# HSIO.net
KiCad netlist of a schematic drawn in EAGLE
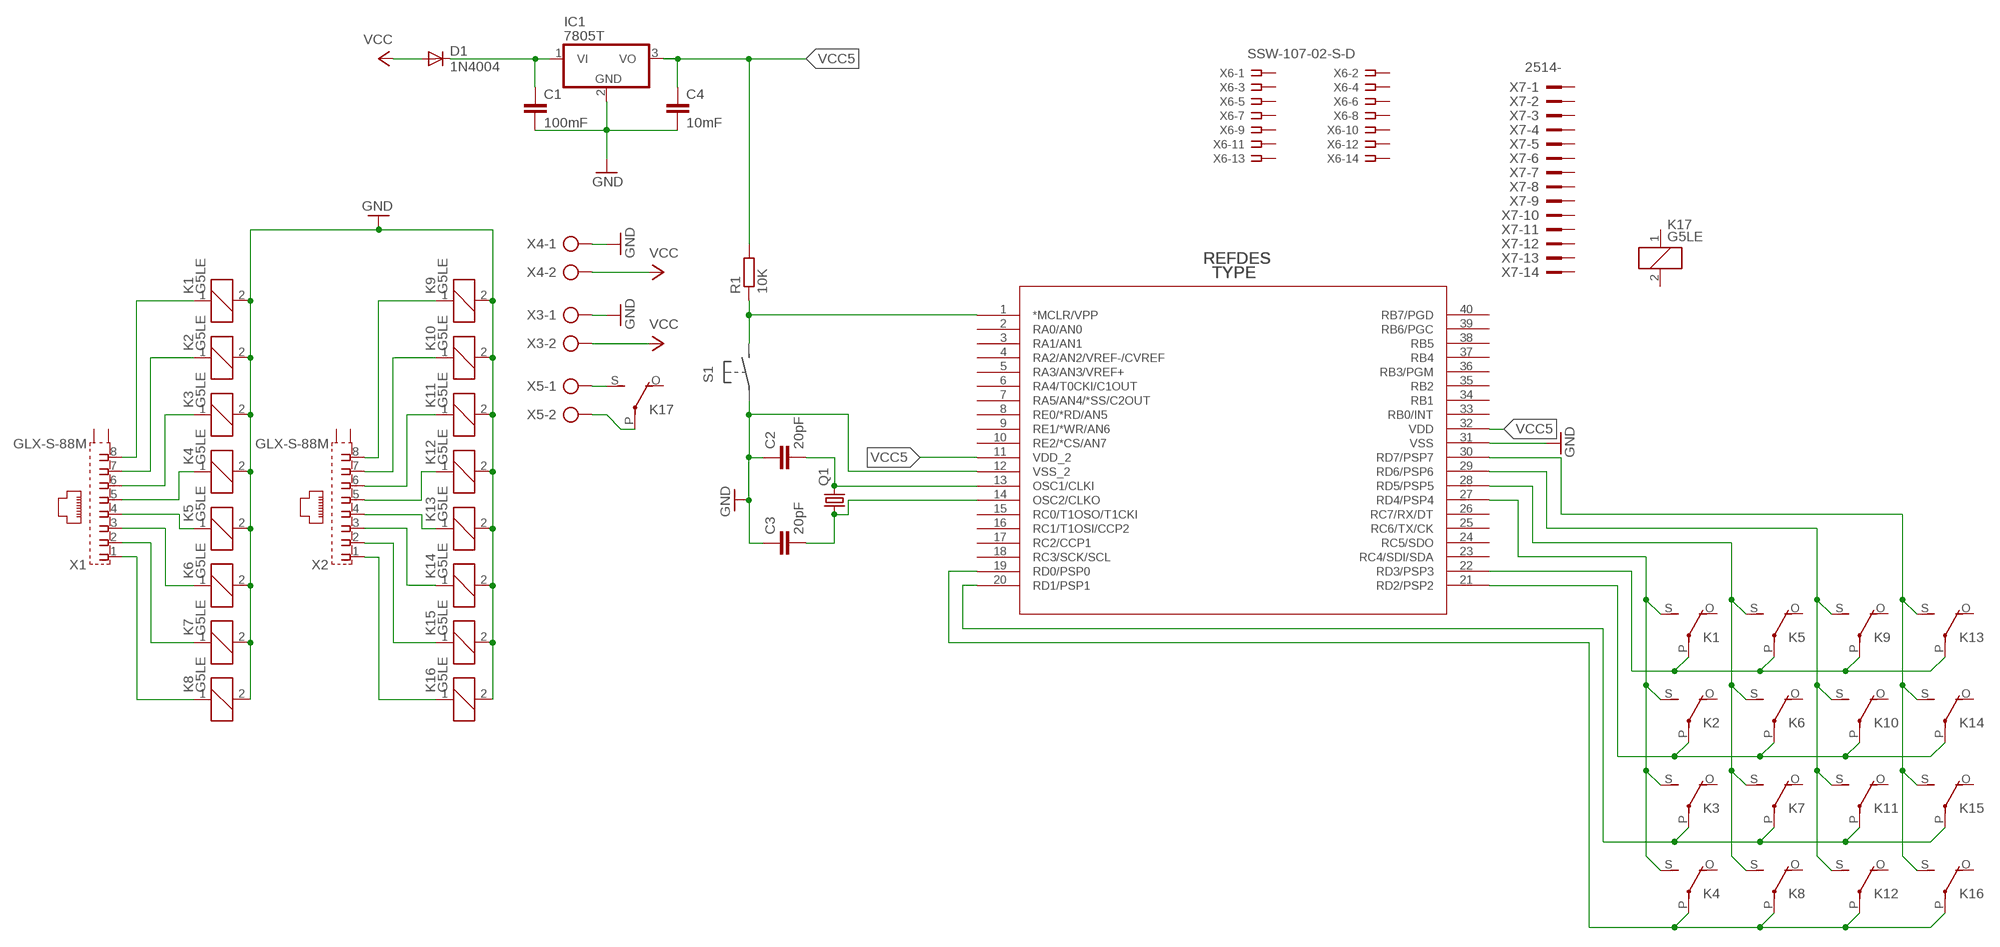
[diagram p0: schematic, sheet 1]

(export (version "E")
  (design (tool "Eeschema 10.0.6"))
  (components
    (comp (ref "C1")
      (value "100mF")
      (footprint "eagle-import:C10B4")
      (libsource (lib "eagle-import") (part "C10/4"))
    )
    (comp (ref "C2")
      (value "20pF")
      (footprint "eagle-import:C10B4")
      (libsource (lib "eagle-import") (part "C10/4"))
    )
    (comp (ref "C3")
      (value "20pF")
      (footprint "eagle-import:C10B4")
      (libsource (lib "eagle-import") (part "C10/4"))
    )
    (comp (ref "C4")
      (value "10mF")
      (footprint "eagle-import:C10B4")
      (libsource (lib "eagle-import") (part "C10/4"))
    )
    (comp (ref "D1")
      (value "1N4004")
      (footprint "eagle-import:DO41-10")
      (libsource (lib "eagle-import") (part "1N4004"))
    )
    (comp (ref "IC1")
      (value "7805T")
      (footprint "eagle-import:TO220H")
      (libsource (lib "eagle-import") (part "78T05"))
    )
    (comp (ref "K1")
      (value "G5LE")
      (footprint "eagle-import:G5LE")
      (libsource (lib "eagle-import") (part "G5LE"))
    )
    (comp (ref "K2")
      (value "G5LE")
      (footprint "eagle-import:G5LE")
      (libsource (lib "eagle-import") (part "G5LE"))
    )
    (comp (ref "K3")
      (value "G5LE")
      (footprint "eagle-import:G5LE")
      (libsource (lib "eagle-import") (part "G5LE"))
    )
    (comp (ref "K4")
      (value "G5LE")
      (footprint "eagle-import:G5LE")
      (libsource (lib "eagle-import") (part "G5LE"))
    )
    (comp (ref "K5")
      (value "G5LE")
      (footprint "eagle-import:G5LE")
      (libsource (lib "eagle-import") (part "G5LE"))
    )
    (comp (ref "K6")
      (value "G5LE")
      (footprint "eagle-import:G5LE")
      (libsource (lib "eagle-import") (part "G5LE"))
    )
    (comp (ref "K7")
      (value "G5LE")
      (footprint "eagle-import:G5LE")
      (libsource (lib "eagle-import") (part "G5LE"))
    )
    (comp (ref "K8")
      (value "G5LE")
      (footprint "eagle-import:G5LE")
      (libsource (lib "eagle-import") (part "G5LE"))
    )
    (comp (ref "K9")
      (value "G5LE")
      (footprint "eagle-import:G5LE")
      (libsource (lib "eagle-import") (part "G5LE"))
    )
    (comp (ref "K10")
      (value "G5LE")
      (footprint "eagle-import:G5LE")
      (libsource (lib "eagle-import") (part "G5LE"))
    )
    (comp (ref "K11")
      (value "G5LE")
      (footprint "eagle-import:G5LE")
      (libsource (lib "eagle-import") (part "G5LE"))
    )
    (comp (ref "K12")
      (value "G5LE")
      (footprint "eagle-import:G5LE")
      (libsource (lib "eagle-import") (part "G5LE"))
    )
    (comp (ref "K13")
      (value "G5LE")
      (footprint "eagle-import:G5LE")
      (libsource (lib "eagle-import") (part "G5LE"))
    )
    (comp (ref "K14")
      (value "G5LE")
      (footprint "eagle-import:G5LE")
      (libsource (lib "eagle-import") (part "G5LE"))
    )
    (comp (ref "K15")
      (value "G5LE")
      (footprint "eagle-import:G5LE")
      (libsource (lib "eagle-import") (part "G5LE"))
    )
    (comp (ref "K16")
      (value "G5LE")
      (footprint "eagle-import:G5LE")
      (libsource (lib "eagle-import") (part "G5LE"))
    )
    (comp (ref "K17")
      (value "G5LE")
      (footprint "eagle-import:G5LE")
      (libsource (lib "eagle-import") (part "G5LE"))
    )
    (comp (ref "Q1")
      (value "CRYSTALHC49S")
      (footprint "eagle-import:HC49_S")
      (libsource (lib "eagle-import") (part "CRYSTALHC49S"))
    )
    (comp (ref "R1")
      (value "10K")
      (footprint "eagle-import:0207_10")
      (libsource (lib "eagle-import") (part "R-EU_0207/10"))
    )
    (comp (ref "U$1")
      (value "PIC16F877A-X/P")
      (footprint "eagle-import:PDIP40_600MC")
      (libsource (lib "eagle-import") (part "PIC16F877A-X/P"))
    )
    (comp (ref "X1")
      (value "GLX-S-88M")
      (footprint "eagle-import:GLX-S-88M")
      (libsource (lib "eagle-import") (part "GLX-S-88M"))
    )
    (comp (ref "X2")
      (value "GLX-S-88M")
      (footprint "eagle-import:GLX-S-88M")
      (libsource (lib "eagle-import") (part "GLX-S-88M"))
    )
    (comp (ref "X3")
      (value "AK300/2")
      (footprint "eagle-import:AK300_2")
      (libsource (lib "eagle-import") (part "AK300/2"))
    )
    (comp (ref "X4")
      (value "AK300/2")
      (footprint "eagle-import:AK300_2")
      (libsource (lib "eagle-import") (part "AK300/2"))
    )
    (comp (ref "X5")
      (value "AK300/2")
      (footprint "eagle-import:AK300_2")
      (libsource (lib "eagle-import") (part "AK300/2"))
    )
    (comp (ref "X6")
      (value "SSW-107-02-S-D")
      (footprint "eagle-import:SSW-107-02-S-D")
      (libsource (lib "eagle-import") (part "SSW-107-02-S-D"))
    )
    (comp (ref "X7")
      (value "2514-")
      (footprint "eagle-import:PAK100_2500-14")
      (libsource (lib "eagle-import") (part "2514-"))
    )
  )
  (nets
    (net (code "1") (name "GND") (class "Default")
      (node (ref "C1") (pin "2") (pinfunction "2_2") (pintype "passive"))
      (node (ref "C2") (pin "1") (pinfunction "1_1") (pintype "passive"))
      (node (ref "C3") (pin "1") (pinfunction "1_1") (pintype "passive"))
      (node (ref "C4") (pin "2") (pinfunction "2_2") (pintype "passive"))
      (node (ref "IC1") (pin "2") (pinfunction "GND_2") (pintype "passive"))
      (node (ref "K1") (pin "2") (pinfunction "2_2") (pintype "passive"))
      (node (ref "K10") (pin "2") (pinfunction "2_2") (pintype "passive"))
      (node (ref "K11") (pin "2") (pinfunction "2_2") (pintype "passive"))
      (node (ref "K12") (pin "2") (pinfunction "2_2") (pintype "passive"))
      (node (ref "K13") (pin "2") (pinfunction "2_2") (pintype "passive"))
      (node (ref "K14") (pin "2") (pinfunction "2_2") (pintype "passive"))
      (node (ref "K15") (pin "2") (pinfunction "2_2") (pintype "passive"))
      (node (ref "K16") (pin "2") (pinfunction "2_2") (pintype "passive"))
      (node (ref "K2") (pin "2") (pinfunction "2_2") (pintype "passive"))
      (node (ref "K3") (pin "2") (pinfunction "2_2") (pintype "passive"))
      (node (ref "K4") (pin "2") (pinfunction "2_2") (pintype "passive"))
      (node (ref "K5") (pin "2") (pinfunction "2_2") (pintype "passive"))
      (node (ref "K6") (pin "2") (pinfunction "2_2") (pintype "passive"))
      (node (ref "K7") (pin "2") (pinfunction "2_2") (pintype "passive"))
      (node (ref "K8") (pin "2") (pinfunction "2_2") (pintype "passive"))
      (node (ref "K9") (pin "2") (pinfunction "2_2") (pintype "passive"))
      (node (ref "U$1") (pin "12") (pinfunction "VSS_2_12") (pintype "passive"))
      (node (ref "U$1") (pin "31") (pinfunction "VSS_31") (pintype "passive"))
      (node (ref "X3") (pin "1") (pinfunction "KL_1") (pintype "passive"))
      (node (ref "X4") (pin "1") (pinfunction "KL_1") (pintype "passive"))
    )
    (net (code "2") (name "Net-(IC1-VI)") (class "Default")
      (node (ref "C1") (pin "1") (pinfunction "1_1") (pintype "passive"))
      (node (ref "D1") (pin "C") (pinfunction "C_C") (pintype "passive"))
      (node (ref "IC1") (pin "1") (pinfunction "VI_1") (pintype "input"))
    )
    (net (code "3") (name "Net-(K1-Pad1)") (class "Default")
      (node (ref "K1") (pin "1") (pinfunction "1_1") (pintype "passive"))
      (node (ref "X1") (pin "8") (pinfunction "8_8") (pintype "passive"))
    )
    (net (code "4") (name "Net-(K2-Pad1)") (class "Default")
      (node (ref "K2") (pin "1") (pinfunction "1_1") (pintype "passive"))
      (node (ref "X1") (pin "7") (pinfunction "7_7") (pintype "passive"))
    )
    (net (code "5") (name "Net-(K3-Pad1)") (class "Default")
      (node (ref "K3") (pin "1") (pinfunction "1_1") (pintype "passive"))
      (node (ref "X1") (pin "6") (pinfunction "6_6") (pintype "passive"))
    )
    (net (code "6") (name "Net-(K4-Pad1)") (class "Default")
      (node (ref "K4") (pin "1") (pinfunction "1_1") (pintype "passive"))
      (node (ref "X1") (pin "5") (pinfunction "5_5") (pintype "passive"))
    )
    (net (code "7") (name "Net-(K5-Pad1)") (class "Default")
      (node (ref "K5") (pin "1") (pinfunction "1_1") (pintype "passive"))
      (node (ref "X1") (pin "4") (pinfunction "4_4") (pintype "passive"))
    )
    (net (code "8") (name "Net-(K6-Pad1)") (class "Default")
      (node (ref "K6") (pin "1") (pinfunction "1_1") (pintype "passive"))
      (node (ref "X1") (pin "3") (pinfunction "3_3") (pintype "passive"))
    )
    (net (code "9") (name "Net-(K7-Pad1)") (class "Default")
      (node (ref "K7") (pin "1") (pinfunction "1_1") (pintype "passive"))
      (node (ref "X1") (pin "2") (pinfunction "2_2") (pintype "passive"))
    )
    (net (code "10") (name "Net-(K8-Pad1)") (class "Default")
      (node (ref "K8") (pin "1") (pinfunction "1_1") (pintype "passive"))
      (node (ref "X1") (pin "1") (pinfunction "1_1") (pintype "passive"))
    )
    (net (code "11") (name "Net-(K9-Pad1)") (class "Default")
      (node (ref "K9") (pin "1") (pinfunction "1_1") (pintype "passive"))
      (node (ref "X2") (pin "8") (pinfunction "8_8") (pintype "passive"))
    )
    (net (code "12") (name "Net-(K10-Pad1)") (class "Default")
      (node (ref "K10") (pin "1") (pinfunction "1_1") (pintype "passive"))
      (node (ref "X2") (pin "7") (pinfunction "7_7") (pintype "passive"))
    )
    (net (code "13") (name "Net-(K11-Pad1)") (class "Default")
      (node (ref "K11") (pin "1") (pinfunction "1_1") (pintype "passive"))
      (node (ref "X2") (pin "6") (pinfunction "6_6") (pintype "passive"))
    )
    (net (code "14") (name "Net-(K12-Pad1)") (class "Default")
      (node (ref "K12") (pin "1") (pinfunction "1_1") (pintype "passive"))
      (node (ref "X2") (pin "5") (pinfunction "5_5") (pintype "passive"))
    )
    (net (code "15") (name "Net-(K13-Pad1)") (class "Default")
      (node (ref "K13") (pin "1") (pinfunction "1_1") (pintype "passive"))
      (node (ref "X2") (pin "4") (pinfunction "4_4") (pintype "passive"))
    )
    (net (code "16") (name "Net-(K14-Pad1)") (class "Default")
      (node (ref "K14") (pin "1") (pinfunction "1_1") (pintype "passive"))
      (node (ref "X2") (pin "3") (pinfunction "3_3") (pintype "passive"))
    )
    (net (code "17") (name "Net-(K15-Pad1)") (class "Default")
      (node (ref "K15") (pin "1") (pinfunction "1_1") (pintype "passive"))
      (node (ref "X2") (pin "2") (pinfunction "2_2") (pintype "passive"))
    )
    (net (code "18") (name "Net-(K16-Pad1)") (class "Default")
      (node (ref "K16") (pin "1") (pinfunction "1_1") (pintype "passive"))
      (node (ref "X2") (pin "1") (pinfunction "1_1") (pintype "passive"))
    )
    (net (code "19") (name "Net-(U$1-*MCLR{slash}VPP)") (class "Default")
      (node (ref "R1") (pin "1") (pinfunction "1_1") (pintype "passive"))
      (node (ref "U$1") (pin "1") (pinfunction "*MCLR/VPP_1") (pintype "passive"))
    )
    (net (code "20") (name "Net-(U$1-OSC1{slash}CLKI)") (class "Default")
      (node (ref "C2") (pin "2") (pinfunction "2_2") (pintype "passive"))
      (node (ref "Q1") (pin "2") (pinfunction "2_2") (pintype "passive"))
      (node (ref "U$1") (pin "13") (pinfunction "OSC1/CLKI_13") (pintype "passive"))
    )
    (net (code "21") (name "Net-(U$1-OSC2{slash}CLKO)") (class "Default")
      (node (ref "C3") (pin "2") (pinfunction "2_2") (pintype "passive"))
      (node (ref "Q1") (pin "1") (pinfunction "1_1") (pintype "passive"))
      (node (ref "U$1") (pin "14") (pinfunction "OSC2/CLKO_14") (pintype "passive"))
    )
    (net (code "22") (name "Net-(U$1-RD0{slash}PSP0)") (class "Default")
      (node (ref "K12") (pin "P") (pinfunction "P_P") (pintype "passive"))
      (node (ref "K16") (pin "P") (pinfunction "P_P") (pintype "passive"))
      (node (ref "K4") (pin "P") (pinfunction "P_P") (pintype "passive"))
      (node (ref "K8") (pin "P") (pinfunction "P_P") (pintype "passive"))
      (node (ref "U$1") (pin "19") (pinfunction "RD0/PSP0_19") (pintype "passive"))
    )
    (net (code "23") (name "Net-(U$1-RD1{slash}PSP1)") (class "Default")
      (node (ref "K11") (pin "P") (pinfunction "P_P") (pintype "passive"))
      (node (ref "K15") (pin "P") (pinfunction "P_P") (pintype "passive"))
      (node (ref "K3") (pin "P") (pinfunction "P_P") (pintype "passive"))
      (node (ref "K7") (pin "P") (pinfunction "P_P") (pintype "passive"))
      (node (ref "U$1") (pin "20") (pinfunction "RD1/PSP1_20") (pintype "passive"))
    )
    (net (code "24") (name "Net-(U$1-RD2{slash}PSP2)") (class "Default")
      (node (ref "K10") (pin "P") (pinfunction "P_P") (pintype "passive"))
      (node (ref "K14") (pin "P") (pinfunction "P_P") (pintype "passive"))
      (node (ref "K2") (pin "P") (pinfunction "P_P") (pintype "passive"))
      (node (ref "K6") (pin "P") (pinfunction "P_P") (pintype "passive"))
      (node (ref "U$1") (pin "21") (pinfunction "RD2/PSP2_21") (pintype "passive"))
    )
    (net (code "25") (name "Net-(U$1-RD3{slash}PSP3)") (class "Default")
      (node (ref "K1") (pin "P") (pinfunction "P_P") (pintype "passive"))
      (node (ref "K13") (pin "P") (pinfunction "P_P") (pintype "passive"))
      (node (ref "K5") (pin "P") (pinfunction "P_P") (pintype "passive"))
      (node (ref "K9") (pin "P") (pinfunction "P_P") (pintype "passive"))
      (node (ref "U$1") (pin "22") (pinfunction "RD3/PSP3_22") (pintype "passive"))
    )
    (net (code "26") (name "Net-(U$1-RD4{slash}PSP4)") (class "Default")
      (node (ref "K1") (pin "S") (pinfunction "S_S") (pintype "passive"))
      (node (ref "K2") (pin "S") (pinfunction "S_S") (pintype "passive"))
      (node (ref "K3") (pin "S") (pinfunction "S_S") (pintype "passive"))
      (node (ref "K4") (pin "S") (pinfunction "S_S") (pintype "passive"))
      (node (ref "U$1") (pin "27") (pinfunction "RD4/PSP4_27") (pintype "passive"))
    )
    (net (code "27") (name "Net-(U$1-RD5{slash}PSP5)") (class "Default")
      (node (ref "K5") (pin "S") (pinfunction "S_S") (pintype "passive"))
      (node (ref "K6") (pin "S") (pinfunction "S_S") (pintype "passive"))
      (node (ref "K7") (pin "S") (pinfunction "S_S") (pintype "passive"))
      (node (ref "K8") (pin "S") (pinfunction "S_S") (pintype "passive"))
      (node (ref "U$1") (pin "28") (pinfunction "RD5/PSP5_28") (pintype "passive"))
    )
    (net (code "28") (name "Net-(U$1-RD6{slash}PSP6)") (class "Default")
      (node (ref "K10") (pin "S") (pinfunction "S_S") (pintype "passive"))
      (node (ref "K11") (pin "S") (pinfunction "S_S") (pintype "passive"))
      (node (ref "K12") (pin "S") (pinfunction "S_S") (pintype "passive"))
      (node (ref "K9") (pin "S") (pinfunction "S_S") (pintype "passive"))
      (node (ref "U$1") (pin "29") (pinfunction "RD6/PSP6_29") (pintype "passive"))
    )
    (net (code "29") (name "Net-(U$1-RD7{slash}PSP7)") (class "Default")
      (node (ref "K13") (pin "S") (pinfunction "S_S") (pintype "passive"))
      (node (ref "K14") (pin "S") (pinfunction "S_S") (pintype "passive"))
      (node (ref "K15") (pin "S") (pinfunction "S_S") (pintype "passive"))
      (node (ref "K16") (pin "S") (pinfunction "S_S") (pintype "passive"))
      (node (ref "U$1") (pin "30") (pinfunction "RD7/PSP7_30") (pintype "passive"))
    )
    (net (code "30") (name "Net-(X5A-KL)") (class "Default")
      (node (ref "K17") (pin "S") (pinfunction "S_S") (pintype "passive"))
      (node (ref "X5") (pin "1") (pinfunction "KL_1") (pintype "passive"))
    )
    (net (code "31") (name "Net-(X5B-KL)") (class "Default")
      (node (ref "K17") (pin "P") (pinfunction "P_P") (pintype "passive"))
      (node (ref "X5") (pin "2") (pinfunction "KL_2") (pintype "passive"))
    )
    (net (code "32") (name "VCC") (class "Default")
      (node (ref "D1") (pin "A") (pinfunction "A_A") (pintype "passive"))
      (node (ref "X3") (pin "2") (pinfunction "KL_2") (pintype "passive"))
      (node (ref "X4") (pin "2") (pinfunction "KL_2") (pintype "passive"))
    )
    (net (code "33") (name "VCC5") (class "Default")
      (node (ref "C4") (pin "1") (pinfunction "1_1") (pintype "passive"))
      (node (ref "IC1") (pin "3") (pinfunction "VO_3") (pintype "passive"))
      (node (ref "R1") (pin "2") (pinfunction "2_2") (pintype "passive"))
      (node (ref "U$1") (pin "11") (pinfunction "VDD_2_11") (pintype "passive"))
      (node (ref "U$1") (pin "32") (pinfunction "VDD_32") (pintype "passive"))
    )
    (net (code "34") (name "unconnected-(K1-PadO)") (class "Default")
      (node (ref "K1") (pin "O") (pinfunction "O_O") (pintype "passive"))
    )
    (net (code "35") (name "unconnected-(K2-PadO)") (class "Default")
      (node (ref "K2") (pin "O") (pinfunction "O_O") (pintype "passive"))
    )
    (net (code "36") (name "unconnected-(K3-PadO)") (class "Default")
      (node (ref "K3") (pin "O") (pinfunction "O_O") (pintype "passive"))
    )
    (net (code "37") (name "unconnected-(K4-PadO)") (class "Default")
      (node (ref "K4") (pin "O") (pinfunction "O_O") (pintype "passive"))
    )
    (net (code "38") (name "unconnected-(K5-PadO)") (class "Default")
      (node (ref "K5") (pin "O") (pinfunction "O_O") (pintype "passive"))
    )
    (net (code "39") (name "unconnected-(K6-PadO)") (class "Default")
      (node (ref "K6") (pin "O") (pinfunction "O_O") (pintype "passive"))
    )
    (net (code "40") (name "unconnected-(K7-PadO)") (class "Default")
      (node (ref "K7") (pin "O") (pinfunction "O_O") (pintype "passive"))
    )
    (net (code "41") (name "unconnected-(K8-PadO)") (class "Default")
      (node (ref "K8") (pin "O") (pinfunction "O_O") (pintype "passive"))
    )
    (net (code "42") (name "unconnected-(K9-PadO)") (class "Default")
      (node (ref "K9") (pin "O") (pinfunction "O_O") (pintype "passive"))
    )
    (net (code "43") (name "unconnected-(K10-PadO)") (class "Default")
      (node (ref "K10") (pin "O") (pinfunction "O_O") (pintype "passive"))
    )
    (net (code "44") (name "unconnected-(K11-PadO)") (class "Default")
      (node (ref "K11") (pin "O") (pinfunction "O_O") (pintype "passive"))
    )
    (net (code "45") (name "unconnected-(K12-PadO)") (class "Default")
      (node (ref "K12") (pin "O") (pinfunction "O_O") (pintype "passive"))
    )
    (net (code "46") (name "unconnected-(K13-PadO)") (class "Default")
      (node (ref "K13") (pin "O") (pinfunction "O_O") (pintype "passive"))
    )
    (net (code "47") (name "unconnected-(K14-PadO)") (class "Default")
      (node (ref "K14") (pin "O") (pinfunction "O_O") (pintype "passive"))
    )
    (net (code "48") (name "unconnected-(K15-PadO)") (class "Default")
      (node (ref "K15") (pin "O") (pinfunction "O_O") (pintype "passive"))
    )
    (net (code "49") (name "unconnected-(K16-PadO)") (class "Default")
      (node (ref "K16") (pin "O") (pinfunction "O_O") (pintype "passive"))
    )
    (net (code "50") (name "unconnected-(K17-Pad1)") (class "Default")
      (node (ref "K17") (pin "1") (pinfunction "1_1") (pintype "passive"))
    )
    (net (code "51") (name "unconnected-(K17-Pad2)") (class "Default")
      (node (ref "K17") (pin "2") (pinfunction "2_2") (pintype "passive"))
    )
    (net (code "52") (name "unconnected-(K17-PadO)") (class "Default")
      (node (ref "K17") (pin "O") (pinfunction "O_O") (pintype "passive"))
    )
    (net (code "53") (name "unconnected-(U$1-RA0{slash}AN0-Pad2)") (class "Default")
      (node (ref "U$1") (pin "2") (pinfunction "RA0/AN0_2") (pintype "passive"))
    )
    (net (code "54") (name "unconnected-(U$1-RA1{slash}AN1-Pad3)") (class "Default")
      (node (ref "U$1") (pin "3") (pinfunction "RA1/AN1_3") (pintype "passive"))
    )
    (net (code "55") (name "unconnected-(U$1-RA2{slash}AN2{slash}VREF-{slash}CVREF-Pad4)") (class "Default")
      (node (ref "U$1") (pin "4") (pinfunction "RA2/AN2/VREF-/CVREF_4") (pintype "passive"))
    )
    (net (code "56") (name "unconnected-(U$1-RA3{slash}AN3{slash}VREF+-Pad5)") (class "Default")
      (node (ref "U$1") (pin "5") (pinfunction "RA3/AN3/VREF+_5") (pintype "passive"))
    )
    (net (code "57") (name "unconnected-(U$1-RA4{slash}T0CKI{slash}C1OUT-Pad6)") (class "Default")
      (node (ref "U$1") (pin "6") (pinfunction "RA4/T0CKI/C1OUT_6") (pintype "passive"))
    )
    (net (code "58") (name "unconnected-(U$1-RA5{slash}AN4{slash}*SS{slash}C2OUT-Pad7)") (class "Default")
      (node (ref "U$1") (pin "7") (pinfunction "RA5/AN4/*SS/C2OUT_7") (pintype "passive"))
    )
    (net (code "59") (name "unconnected-(U$1-RB0{slash}INT-Pad33)") (class "Default")
      (node (ref "U$1") (pin "33") (pinfunction "RB0/INT_33") (pintype "passive"))
    )
    (net (code "60") (name "unconnected-(U$1-RB1-Pad34)") (class "Default")
      (node (ref "U$1") (pin "34") (pinfunction "RB1_34") (pintype "passive"))
    )
    (net (code "61") (name "unconnected-(U$1-RB2-Pad35)") (class "Default")
      (node (ref "U$1") (pin "35") (pinfunction "RB2_35") (pintype "passive"))
    )
    (net (code "62") (name "unconnected-(U$1-RB3{slash}PGM-Pad36)") (class "Default")
      (node (ref "U$1") (pin "36") (pinfunction "RB3/PGM_36") (pintype "passive"))
    )
    (net (code "63") (name "unconnected-(U$1-RB4-Pad37)") (class "Default")
      (node (ref "U$1") (pin "37") (pinfunction "RB4_37") (pintype "passive"))
    )
    (net (code "64") (name "unconnected-(U$1-RB5-Pad38)") (class "Default")
      (node (ref "U$1") (pin "38") (pinfunction "RB5_38") (pintype "passive"))
    )
    (net (code "65") (name "unconnected-(U$1-RB6{slash}PGC-Pad39)") (class "Default")
      (node (ref "U$1") (pin "39") (pinfunction "RB6/PGC_39") (pintype "passive"))
    )
    (net (code "66") (name "unconnected-(U$1-RB7{slash}PGD-Pad40)") (class "Default")
      (node (ref "U$1") (pin "40") (pinfunction "RB7/PGD_40") (pintype "passive"))
    )
    (net (code "67") (name "unconnected-(U$1-RC0{slash}T1OSO{slash}T1CKI-Pad15)") (class "Default")
      (node (ref "U$1") (pin "15") (pinfunction "RC0/T1OSO/T1CKI_15") (pintype "passive"))
    )
    (net (code "68") (name "unconnected-(U$1-RC1{slash}T1OSI{slash}CCP2-Pad16)") (class "Default")
      (node (ref "U$1") (pin "16") (pinfunction "RC1/T1OSI/CCP2_16") (pintype "passive"))
    )
    (net (code "69") (name "unconnected-(U$1-RC2{slash}CCP1-Pad17)") (class "Default")
      (node (ref "U$1") (pin "17") (pinfunction "RC2/CCP1_17") (pintype "passive"))
    )
    (net (code "70") (name "unconnected-(U$1-RC3{slash}SCK{slash}SCL-Pad18)") (class "Default")
      (node (ref "U$1") (pin "18") (pinfunction "RC3/SCK/SCL_18") (pintype "passive"))
    )
    (net (code "71") (name "unconnected-(U$1-RC4{slash}SDI{slash}SDA-Pad23)") (class "Default")
      (node (ref "U$1") (pin "23") (pinfunction "RC4/SDI/SDA_23") (pintype "passive"))
    )
    (net (code "72") (name "unconnected-(U$1-RC5{slash}SDO-Pad24)") (class "Default")
      (node (ref "U$1") (pin "24") (pinfunction "RC5/SDO_24") (pintype "passive"))
    )
    (net (code "73") (name "unconnected-(U$1-RC6{slash}TX{slash}CK-Pad25)") (class "Default")
      (node (ref "U$1") (pin "25") (pinfunction "RC6/TX/CK_25") (pintype "passive"))
    )
    (net (code "74") (name "unconnected-(U$1-RC7{slash}RX{slash}DT-Pad26)") (class "Default")
      (node (ref "U$1") (pin "26") (pinfunction "RC7/RX/DT_26") (pintype "passive"))
    )
    (net (code "75") (name "unconnected-(U$1-RE0{slash}*RD{slash}AN5-Pad8)") (class "Default")
      (node (ref "U$1") (pin "8") (pinfunction "RE0/*RD/AN5_8") (pintype "passive"))
    )
    (net (code "76") (name "unconnected-(U$1-RE1{slash}*WR{slash}AN6-Pad9)") (class "Default")
      (node (ref "U$1") (pin "9") (pinfunction "RE1/*WR/AN6_9") (pintype "passive"))
    )
    (net (code "77") (name "unconnected-(U$1-RE2{slash}*CS{slash}AN7-Pad10)") (class "Default")
      (node (ref "U$1") (pin "10") (pinfunction "RE2/*CS/AN7_10") (pintype "passive"))
    )
    (net (code "78") (name "unconnected-(X1-PadS1)") (class "Default")
      (node (ref "X1") (pin "S1") (pinfunction "S1_S1") (pintype "passive"))
    )
    (net (code "79") (name "unconnected-(X1-PadS2)") (class "Default")
      (node (ref "X1") (pin "S2") (pinfunction "S2_S2") (pintype "passive"))
    )
    (net (code "80") (name "unconnected-(X2-PadS1)") (class "Default")
      (node (ref "X2") (pin "S1") (pinfunction "S1_S1") (pintype "passive"))
    )
    (net (code "81") (name "unconnected-(X2-PadS2)") (class "Default")
      (node (ref "X2") (pin "S2") (pinfunction "S2_S2") (pintype "passive"))
    )
    (net (code "82") (name "unconnected-(X6-Pad1)") (class "Default")
      (node (ref "X6") (pin "1") (pinfunction "1_1") (pintype "passive"))
    )
    (net (code "83") (name "unconnected-(X6B-1-Pad10)") (class "Default")
      (node (ref "X6") (pin "10") (pinfunction "1_10") (pintype "passive"))
    )
    (net (code "84") (name "unconnected-(X6C-1-Pad11)") (class "Default")
      (node (ref "X6") (pin "11") (pinfunction "1_11") (pintype "passive"))
    )
    (net (code "85") (name "unconnected-(X6D-1-Pad12)") (class "Default")
      (node (ref "X6") (pin "12") (pinfunction "1_12") (pintype "passive"))
    )
    (net (code "86") (name "unconnected-(X6E-1-Pad13)") (class "Default")
      (node (ref "X6") (pin "13") (pinfunction "1_13") (pintype "passive"))
    )
    (net (code "87") (name "unconnected-(X6F-1-Pad14)") (class "Default")
      (node (ref "X6") (pin "14") (pinfunction "1_14") (pintype "passive"))
    )
    (net (code "88") (name "unconnected-(X6G-1-Pad2)") (class "Default")
      (node (ref "X6") (pin "2") (pinfunction "1_2") (pintype "passive"))
    )
    (net (code "89") (name "unconnected-(X6H-1-Pad3)") (class "Default")
      (node (ref "X6") (pin "3") (pinfunction "1_3") (pintype "passive"))
    )
    (net (code "90") (name "unconnected-(X6I-1-Pad4)") (class "Default")
      (node (ref "X6") (pin "4") (pinfunction "1_4") (pintype "passive"))
    )
    (net (code "91") (name "unconnected-(X6J-1-Pad5)") (class "Default")
      (node (ref "X6") (pin "5") (pinfunction "1_5") (pintype "passive"))
    )
    (net (code "92") (name "unconnected-(X6K-1-Pad6)") (class "Default")
      (node (ref "X6") (pin "6") (pinfunction "1_6") (pintype "passive"))
    )
    (net (code "93") (name "unconnected-(X6L-1-Pad7)") (class "Default")
      (node (ref "X6") (pin "7") (pinfunction "1_7") (pintype "passive"))
    )
    (net (code "94") (name "unconnected-(X6M-1-Pad8)") (class "Default")
      (node (ref "X6") (pin "8") (pinfunction "1_8") (pintype "passive"))
    )
    (net (code "95") (name "unconnected-(X6N-1-Pad9)") (class "Default")
      (node (ref "X6") (pin "9") (pinfunction "1_9") (pintype "passive"))
    )
    (net (code "96") (name "unconnected-(X7A-KL-Pad1)") (class "Default")
      (node (ref "X7") (pin "1") (pinfunction "KL_1") (pintype "passive"))
    )
    (net (code "97") (name "unconnected-(X7B-KL-Pad10)") (class "Default")
      (node (ref "X7") (pin "10") (pinfunction "KL_10") (pintype "passive"))
    )
    (net (code "98") (name "unconnected-(X7C-KL-Pad11)") (class "Default")
      (node (ref "X7") (pin "11") (pinfunction "KL_11") (pintype "passive"))
    )
    (net (code "99") (name "unconnected-(X7D-KL-Pad12)") (class "Default")
      (node (ref "X7") (pin "12") (pinfunction "KL_12") (pintype "passive"))
    )
    (net (code "100") (name "unconnected-(X7E-KL-Pad13)") (class "Default")
      (node (ref "X7") (pin "13") (pinfunction "KL_13") (pintype "passive"))
    )
    (net (code "101") (name "unconnected-(X7F-KL-Pad14)") (class "Default")
      (node (ref "X7") (pin "14") (pinfunction "KL_14") (pintype "passive"))
    )
    (net (code "102") (name "unconnected-(X7G-KL-Pad2)") (class "Default")
      (node (ref "X7") (pin "2") (pinfunction "KL_2") (pintype "passive"))
    )
    (net (code "103") (name "unconnected-(X7H-KL-Pad3)") (class "Default")
      (node (ref "X7") (pin "3") (pinfunction "KL_3") (pintype "passive"))
    )
    (net (code "104") (name "unconnected-(X7I-KL-Pad4)") (class "Default")
      (node (ref "X7") (pin "4") (pinfunction "KL_4") (pintype "passive"))
    )
    (net (code "105") (name "unconnected-(X7J-KL-Pad5)") (class "Default")
      (node (ref "X7") (pin "5") (pinfunction "KL_5") (pintype "passive"))
    )
    (net (code "106") (name "unconnected-(X7K-KL-Pad6)") (class "Default")
      (node (ref "X7") (pin "6") (pinfunction "KL_6") (pintype "passive"))
    )
    (net (code "107") (name "unconnected-(X7L-KL-Pad7)") (class "Default")
      (node (ref "X7") (pin "7") (pinfunction "KL_7") (pintype "passive"))
    )
    (net (code "108") (name "unconnected-(X7M-KL-Pad8)") (class "Default")
      (node (ref "X7") (pin "8") (pinfunction "KL_8") (pintype "passive"))
    )
    (net (code "109") (name "unconnected-(X7N-KL-Pad9)") (class "Default")
      (node (ref "X7") (pin "9") (pinfunction "KL_9") (pintype "passive"))
    )
  )
)
